# ESP1.net
KiCad netlist of a schematic drawn in EAGLE
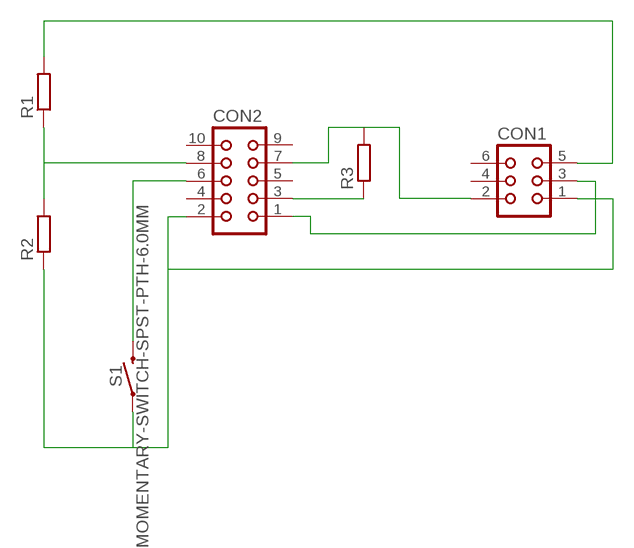
[diagram p0: schematic, sheet 1]

(export (version "E")
  (design (tool "Eeschema 10.0.6"))
  (components
    (comp (ref "CON1")
      (value "CON06L")
      (footprint "eagle-import:CON06L")
      (libsource (lib "eagle-import") (part "CON06L"))
    )
    (comp (ref "CON2")
      (value "CON10L")
      (footprint "eagle-import:CON10L")
      (libsource (lib "eagle-import") (part "CON10L"))
    )
    (comp (ref "R1")
      (value "R-EU_0204/7")
      (footprint "eagle-import:0204_7")
      (libsource (lib "eagle-import") (part "R-EU_0204/7"))
    )
    (comp (ref "R2")
      (value "R-EU_0204/7")
      (footprint "eagle-import:0204_7")
      (libsource (lib "eagle-import") (part "R-EU_0204/7"))
    )
    (comp (ref "R3")
      (value "R-EU_0204/7")
      (footprint "eagle-import:0204_7")
      (libsource (lib "eagle-import") (part "R-EU_0204/7"))
    )
    (comp (ref "S1")
      (value "MOMENTARY-SWITCH-SPST-PTH-6.0MM")
      (footprint "eagle-import:TACTILE_SWITCH_PTH_6.0MM")
      (libsource (lib "eagle-import") (part "MOMENTARY-SWITCH-SPST-PTH-6.0MM"))
    )
  )
  (nets
    (net (code "1") (name "Net-(CON1-Pad1)") (class "Default")
      (node (ref "CON1") (pin "1") (pinfunction "1_1") (pintype "passive"))
      (node (ref "CON2") (pin "2") (pinfunction "2_2") (pintype "passive"))
      (node (ref "R2") (pin "1") (pinfunction "1_1") (pintype "passive"))
      (node (ref "S1") (pin "1") (pinfunction "1_1") (pintype "passive"))
    )
    (net (code "2") (name "Net-(CON1-Pad2)") (class "Default")
      (node (ref "CON1") (pin "2") (pinfunction "2_2") (pintype "passive"))
      (node (ref "CON2") (pin "7") (pinfunction "7_7") (pintype "passive"))
      (node (ref "R3") (pin "2") (pinfunction "2_2") (pintype "passive"))
    )
    (net (code "3") (name "Net-(CON1-Pad3)") (class "Default")
      (node (ref "CON1") (pin "3") (pinfunction "3_3") (pintype "passive"))
      (node (ref "CON2") (pin "1") (pinfunction "1_1") (pintype "passive"))
    )
    (net (code "4") (name "Net-(CON1-Pad5)") (class "Default")
      (node (ref "CON1") (pin "5") (pinfunction "5_5") (pintype "passive"))
      (node (ref "R1") (pin "2") (pinfunction "2_2") (pintype "passive"))
    )
    (net (code "5") (name "Net-(CON2-Pad3)") (class "Default")
      (node (ref "CON2") (pin "3") (pinfunction "3_3") (pintype "passive"))
      (node (ref "R3") (pin "1") (pinfunction "1_1") (pintype "passive"))
    )
    (net (code "6") (name "Net-(CON2-Pad8)") (class "Default")
      (node (ref "CON2") (pin "8") (pinfunction "8_8") (pintype "passive"))
      (node (ref "R1") (pin "1") (pinfunction "1_1") (pintype "passive"))
      (node (ref "R2") (pin "2") (pinfunction "2_2") (pintype "passive"))
    )
    (net (code "7") (name "Net-(S1-2)") (class "Default")
      (node (ref "CON2") (pin "6") (pinfunction "6_6") (pintype "passive"))
      (node (ref "S1") (pin "3") (pinfunction "2_3") (pintype "passive"))
    )
    (net (code "8") (name "unconnected-(CON1-Pad4)") (class "Default")
      (node (ref "CON1") (pin "4") (pinfunction "4_4") (pintype "passive"))
    )
    (net (code "9") (name "unconnected-(CON1-Pad6)") (class "Default")
      (node (ref "CON1") (pin "6") (pinfunction "6_6") (pintype "passive"))
    )
    (net (code "10") (name "unconnected-(CON2-Pad4)") (class "Default")
      (node (ref "CON2") (pin "4") (pinfunction "4_4") (pintype "passive"))
    )
    (net (code "11") (name "unconnected-(CON2-Pad5)") (class "Default")
      (node (ref "CON2") (pin "5") (pinfunction "5_5") (pintype "passive"))
    )
    (net (code "12") (name "unconnected-(CON2-Pad9)") (class "Default")
      (node (ref "CON2") (pin "9") (pinfunction "9_9") (pintype "passive"))
    )
    (net (code "13") (name "unconnected-(CON2-Pad10)") (class "Default")
      (node (ref "CON2") (pin "10") (pinfunction "10_10") (pintype "passive"))
    )
  )
)
